# CircuitClockSchematic.net
KiCad netlist of a schematic drawn in EAGLE
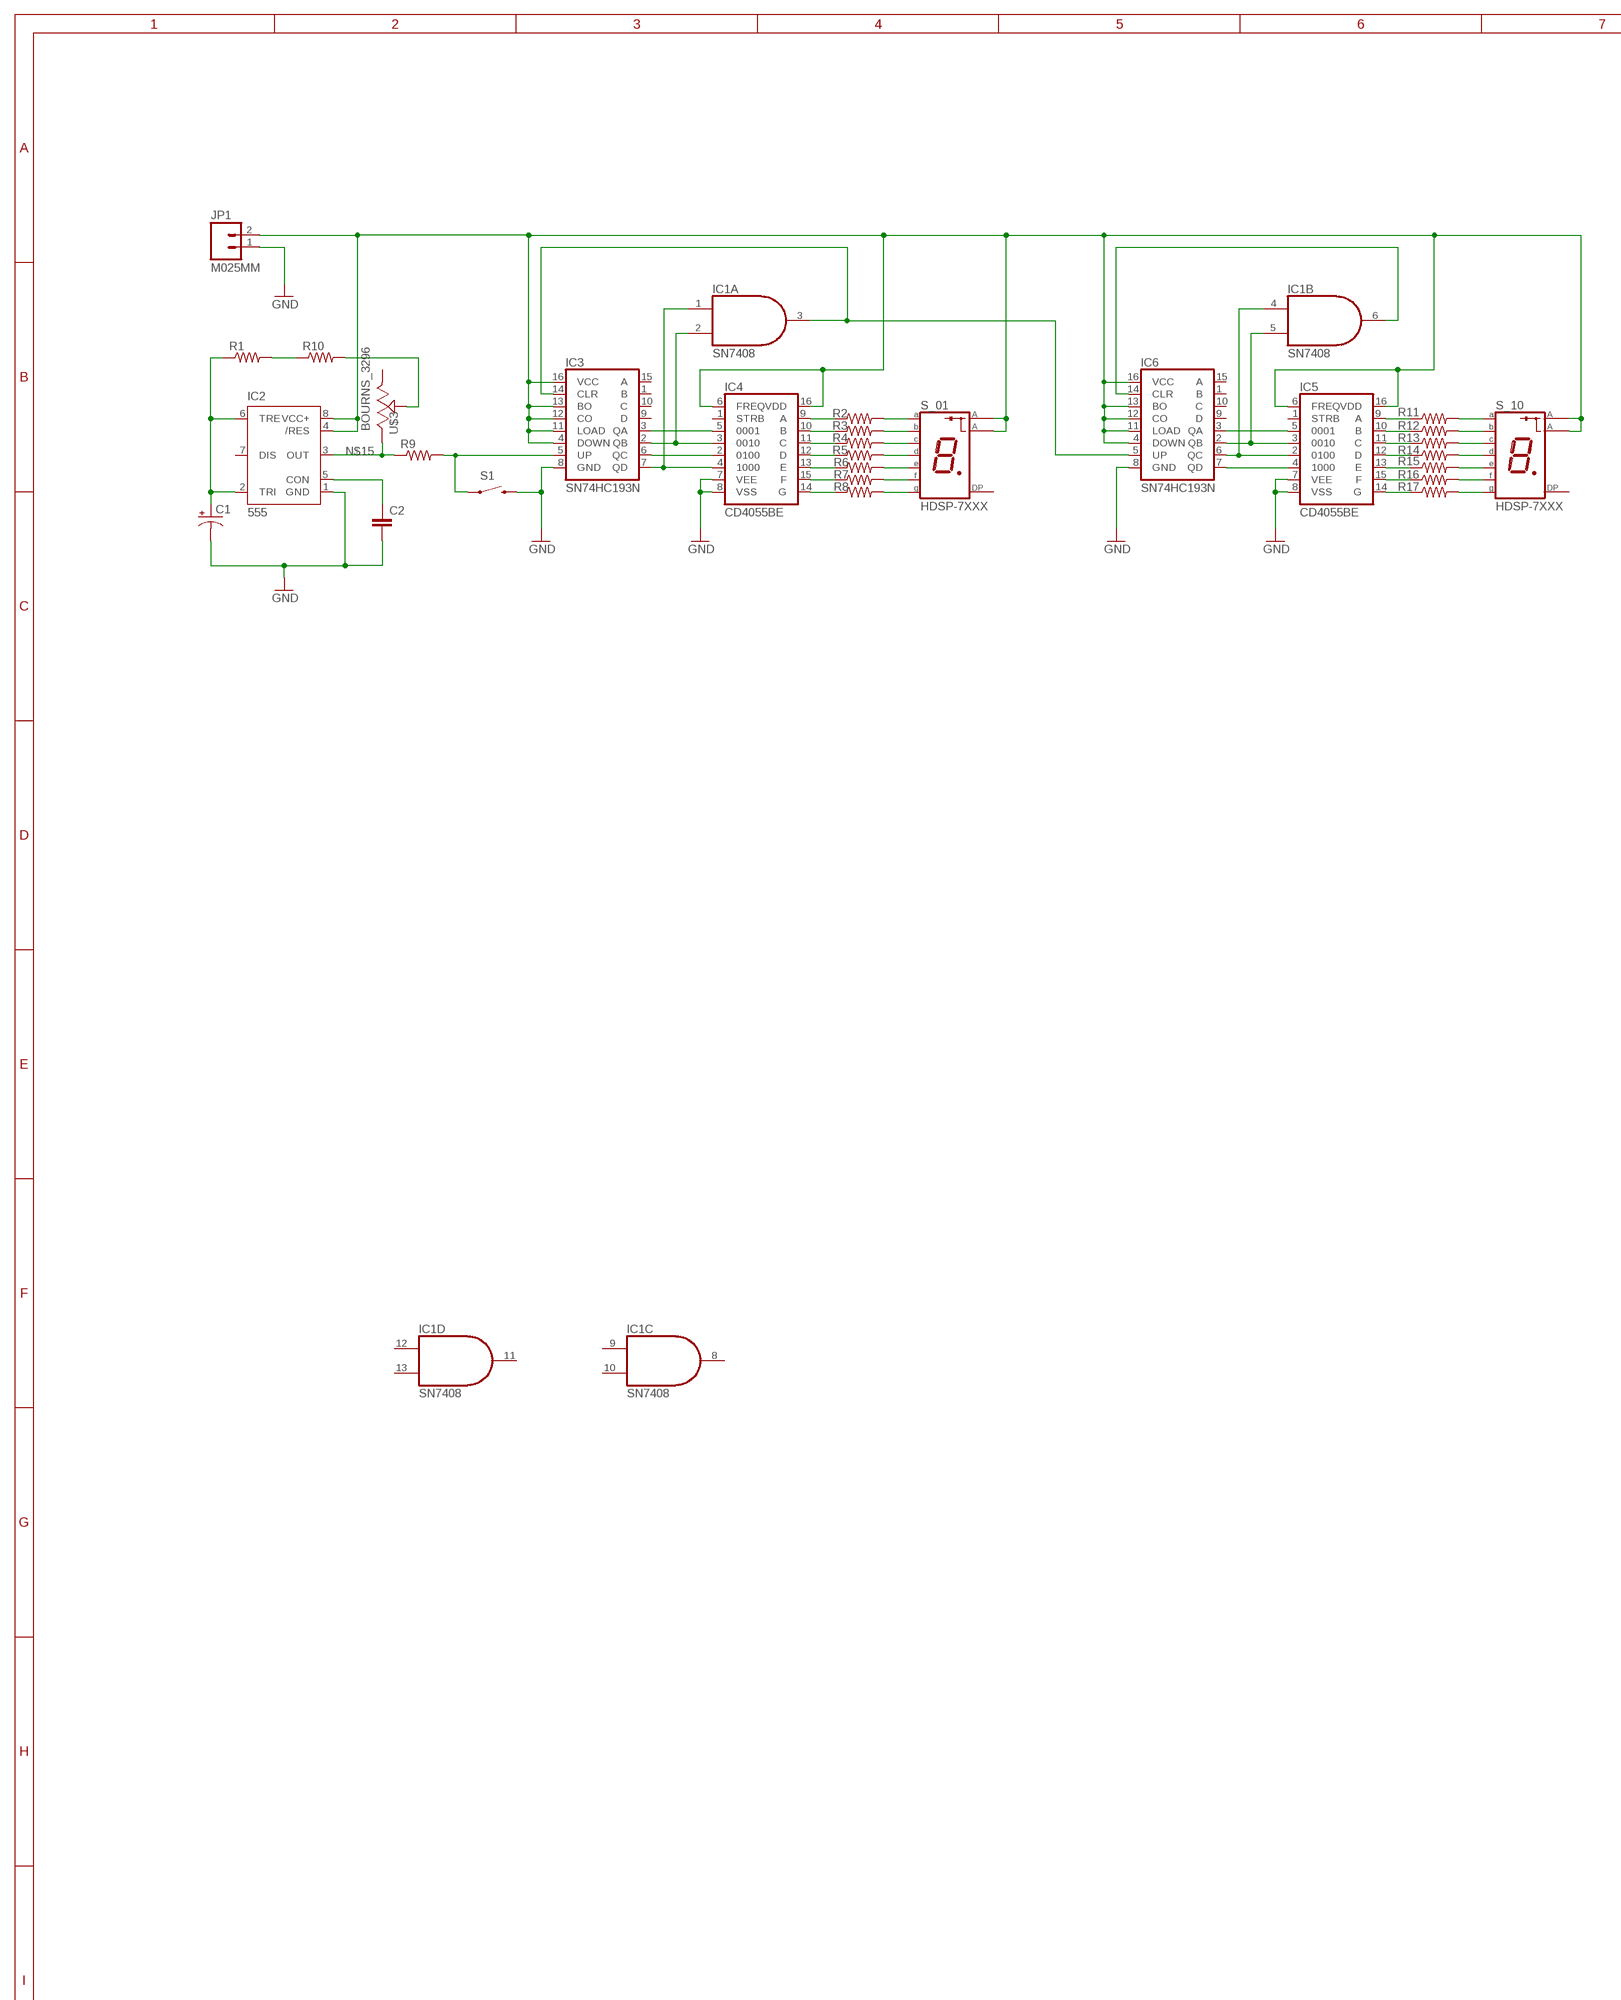
[diagram p0: schematic, sheet 1, part 1 of 2]
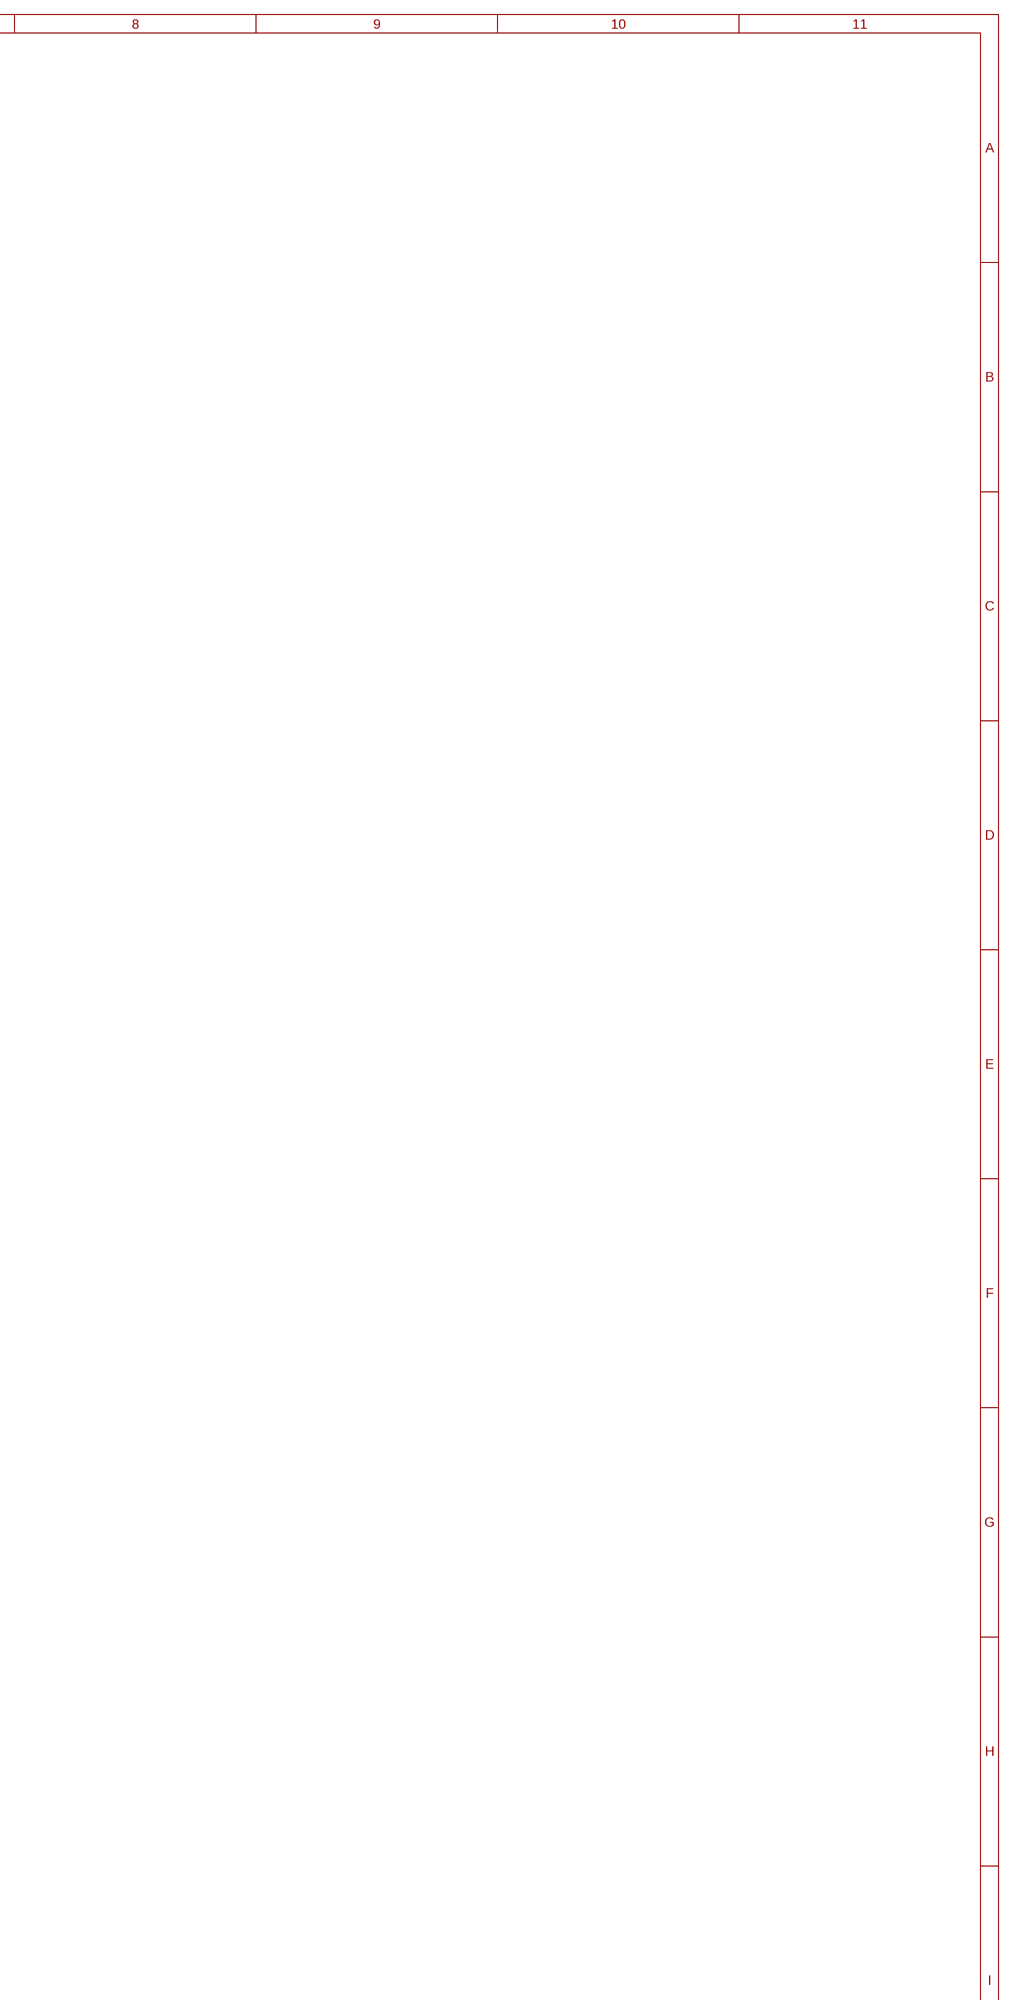
[diagram p1: schematic, sheet 1, part 2 of 2]

(export (version "E")
  (design (tool "Eeschema 10.0.6"))
  (components
    (comp (ref "C1")
      (value "RADIAL_POL2.54MM_LEAD-6.3MM_DIA")
      (footprint "eagle-import:2.54MM_LEAD-6.3MM_DIA")
      (libsource (lib "eagle-import") (part "RADIAL_POL2.54MM_LEAD-6.3MM_DIA"))
    )
    (comp (ref "C2")
      (value "CAPPTH")
      (footprint "eagle-import:CAP-PTH-SMALL")
      (libsource (lib "eagle-import") (part "CAPPTH"))
    )
    (comp (ref "IC1")
      (value "SN7408")
      (footprint "eagle-import:DIL14")
      (libsource (lib "eagle-import") (part "7408NS"))
    )
    (comp (ref "IC2")
      (value "555")
      (footprint "eagle-import:DIP08-KIT")
      (libsource (lib "eagle-import") (part "555KIT"))
    )
    (comp (ref "IC3")
      (value "SN74HC193N")
      (footprint "eagle-import:DIL16")
      (libsource (lib "eagle-import") (part "SN74HC193N"))
    )
    (comp (ref "IC4")
      (value "CD4055BE")
      (footprint "eagle-import:DIL16")
      (libsource (lib "eagle-import") (part "CD4055BE"))
    )
    (comp (ref "IC5")
      (value "CD4055BE")
      (footprint "eagle-import:DIL16")
      (libsource (lib "eagle-import") (part "CD4055BE"))
    )
    (comp (ref "IC6")
      (value "SN74HC193N")
      (footprint "eagle-import:DIL16")
      (libsource (lib "eagle-import") (part "SN74HC193N"))
    )
    (comp (ref "JP1")
      (value "M025MM")
      (footprint "eagle-import:SCREWTERMINAL-5MM-2")
      (libsource (lib "eagle-import") (part "M025MM"))
    )
    (comp (ref "R1")
      (value "RESISTORAXIAL-0.3")
      (footprint "eagle-import:AXIAL-0.3")
      (libsource (lib "eagle-import") (part "RESISTORAXIAL-0.3"))
    )
    (comp (ref "R2")
      (value "RESISTORAXIAL-0.3")
      (footprint "eagle-import:AXIAL-0.3")
      (libsource (lib "eagle-import") (part "RESISTORAXIAL-0.3"))
    )
    (comp (ref "R3")
      (value "RESISTORAXIAL-0.3")
      (footprint "eagle-import:AXIAL-0.3")
      (libsource (lib "eagle-import") (part "RESISTORAXIAL-0.3"))
    )
    (comp (ref "R4")
      (value "RESISTORAXIAL-0.3")
      (footprint "eagle-import:AXIAL-0.3")
      (libsource (lib "eagle-import") (part "RESISTORAXIAL-0.3"))
    )
    (comp (ref "R5")
      (value "RESISTORAXIAL-0.3")
      (footprint "eagle-import:AXIAL-0.3")
      (libsource (lib "eagle-import") (part "RESISTORAXIAL-0.3"))
    )
    (comp (ref "R6")
      (value "RESISTORAXIAL-0.3")
      (footprint "eagle-import:AXIAL-0.3")
      (libsource (lib "eagle-import") (part "RESISTORAXIAL-0.3"))
    )
    (comp (ref "R7")
      (value "RESISTORAXIAL-0.3")
      (footprint "eagle-import:AXIAL-0.3")
      (libsource (lib "eagle-import") (part "RESISTORAXIAL-0.3"))
    )
    (comp (ref "R8")
      (value "RESISTORAXIAL-0.3")
      (footprint "eagle-import:AXIAL-0.3")
      (libsource (lib "eagle-import") (part "RESISTORAXIAL-0.3"))
    )
    (comp (ref "R9")
      (value "RESISTORAXIAL-0.3")
      (footprint "eagle-import:AXIAL-0.3")
      (libsource (lib "eagle-import") (part "RESISTORAXIAL-0.3"))
    )
    (comp (ref "R10")
      (value "RESISTORAXIAL-0.3")
      (footprint "eagle-import:AXIAL-0.3")
      (libsource (lib "eagle-import") (part "RESISTORAXIAL-0.3"))
    )
    (comp (ref "R11")
      (value "RESISTORAXIAL-0.3")
      (footprint "eagle-import:AXIAL-0.3")
      (libsource (lib "eagle-import") (part "RESISTORAXIAL-0.3"))
    )
    (comp (ref "R12")
      (value "RESISTORAXIAL-0.3")
      (footprint "eagle-import:AXIAL-0.3")
      (libsource (lib "eagle-import") (part "RESISTORAXIAL-0.3"))
    )
    (comp (ref "R13")
      (value "RESISTORAXIAL-0.3")
      (footprint "eagle-import:AXIAL-0.3")
      (libsource (lib "eagle-import") (part "RESISTORAXIAL-0.3"))
    )
    (comp (ref "R14")
      (value "RESISTORAXIAL-0.3")
      (footprint "eagle-import:AXIAL-0.3")
      (libsource (lib "eagle-import") (part "RESISTORAXIAL-0.3"))
    )
    (comp (ref "R15")
      (value "RESISTORAXIAL-0.3")
      (footprint "eagle-import:AXIAL-0.3")
      (libsource (lib "eagle-import") (part "RESISTORAXIAL-0.3"))
    )
    (comp (ref "R16")
      (value "RESISTORAXIAL-0.3")
      (footprint "eagle-import:AXIAL-0.3")
      (libsource (lib "eagle-import") (part "RESISTORAXIAL-0.3"))
    )
    (comp (ref "R17")
      (value "RESISTORAXIAL-0.3")
      (footprint "eagle-import:AXIAL-0.3")
      (libsource (lib "eagle-import") (part "RESISTORAXIAL-0.3"))
    )
    (comp (ref "S1")
      (value "SWITCH-MOMENTARY-2PTH")
      (footprint "eagle-import:TACTILE-PTH")
      (libsource (lib "eagle-import") (part "SWITCH-MOMENTARY-2PTH"))
    )
    (comp (ref "S_01")
      (value "HDSP-7XXX")
      (footprint "eagle-import:HDSP-7XXX")
      (libsource (lib "eagle-import") (part "HDSP-7XXX"))
    )
    (comp (ref "S_10")
      (value "HDSP-7XXX")
      (footprint "eagle-import:HDSP-7XXX")
      (libsource (lib "eagle-import") (part "HDSP-7XXX"))
    )
    (comp (ref "U$3")
      (value "BOURNS_3296")
      (footprint "eagle-import:3296")
      (libsource (lib "eagle-import") (part "BOURNS_3296"))
    )
  )
  (nets
    (net (code "1") (name "/N$15") (class "Default")
      (node (ref "IC2") (pin "3") (pinfunction "OUT_3") (pintype "output"))
      (node (ref "R9") (pin "P$1") (pinfunction "1_P$1") (pintype "passive"))
      (node (ref "U$3") (pin "1") (pinfunction "A_1") (pintype "passive"))
    )
    (net (code "2") (name "GND") (class "Default")
      (node (ref "C1") (pin "-") (pinfunction "-_-") (pintype "passive"))
      (node (ref "C2") (pin "2") (pinfunction "2_2") (pintype "passive"))
      (node (ref "IC2") (pin "1") (pinfunction "GND_1") (pintype "power_in"))
      (node (ref "IC3") (pin "8") (pinfunction "GND_8") (pintype "power_in"))
      (node (ref "IC4") (pin "7") (pinfunction "VEE_7") (pintype "bidirectional"))
      (node (ref "IC4") (pin "8") (pinfunction "VSS_8") (pintype "power_in"))
      (node (ref "IC5") (pin "7") (pinfunction "VEE_7") (pintype "bidirectional"))
      (node (ref "IC5") (pin "8") (pinfunction "VSS_8") (pintype "power_in"))
      (node (ref "IC6") (pin "8") (pinfunction "GND_8") (pintype "power_in"))
      (node (ref "JP1") (pin "1") (pinfunction "1_1") (pintype "passive"))
      (node (ref "S1") (pin "3") (pinfunction "2_3") (pintype "passive"))
    )
    (net (code "3") (name "Net-(IC1A-I0)") (class "Default")
      (node (ref "IC1") (pin "1") (pinfunction "I0_1") (pintype "input"))
      (node (ref "IC3") (pin "7") (pinfunction "QD_7") (pintype "bidirectional"))
      (node (ref "IC4") (pin "4") (pinfunction "1000_4") (pintype "bidirectional"))
    )
    (net (code "4") (name "Net-(IC1A-I1)") (class "Default")
      (node (ref "IC1") (pin "2") (pinfunction "I1_2") (pintype "input"))
      (node (ref "IC3") (pin "2") (pinfunction "QB_2") (pintype "bidirectional"))
      (node (ref "IC4") (pin "3") (pinfunction "0010_3") (pintype "input"))
    )
    (net (code "5") (name "Net-(IC1A-O)") (class "Default")
      (node (ref "IC1") (pin "3") (pinfunction "O_3") (pintype "output"))
      (node (ref "IC3") (pin "14") (pinfunction "CLR_14") (pintype "bidirectional"))
      (node (ref "IC6") (pin "5") (pinfunction "UP_5") (pintype "bidirectional"))
    )
    (net (code "6") (name "Net-(IC1B-I0)") (class "Default")
      (node (ref "IC1") (pin "4") (pinfunction "I0_4") (pintype "input"))
      (node (ref "IC5") (pin "2") (pinfunction "0100_2") (pintype "input"))
      (node (ref "IC6") (pin "6") (pinfunction "QC_6") (pintype "bidirectional"))
    )
    (net (code "7") (name "Net-(IC1B-I1)") (class "Default")
      (node (ref "IC1") (pin "5") (pinfunction "I1_5") (pintype "input"))
      (node (ref "IC5") (pin "3") (pinfunction "0010_3") (pintype "input"))
      (node (ref "IC6") (pin "2") (pinfunction "QB_2") (pintype "bidirectional"))
    )
    (net (code "8") (name "Net-(IC1B-O)") (class "Default")
      (node (ref "IC1") (pin "6") (pinfunction "O_6") (pintype "output"))
      (node (ref "IC6") (pin "14") (pinfunction "CLR_14") (pintype "bidirectional"))
    )
    (net (code "9") (name "Net-(IC2-CON)") (class "Default")
      (node (ref "C2") (pin "1") (pinfunction "1_1") (pintype "passive"))
      (node (ref "IC2") (pin "5") (pinfunction "CON_5") (pintype "input"))
    )
    (net (code "10") (name "Net-(IC2-TRE)") (class "Default")
      (node (ref "C1") (pin "+") (pinfunction "+_+") (pintype "passive"))
      (node (ref "IC2") (pin "2") (pinfunction "TRI_2") (pintype "input"))
      (node (ref "IC2") (pin "6") (pinfunction "TRE_6") (pintype "input"))
      (node (ref "R1") (pin "P$1") (pinfunction "1_P$1") (pintype "passive"))
    )
    (net (code "11") (name "Net-(IC2-VCC+)") (class "Default")
      (node (ref "IC2") (pin "4") (pinfunction "/RES_4") (pintype "input"))
      (node (ref "IC2") (pin "8") (pinfunction "VCC+_8") (pintype "power_in"))
      (node (ref "IC3") (pin "11") (pinfunction "LOAD_11") (pintype "input"))
      (node (ref "IC3") (pin "12") (pinfunction "CO_12") (pintype "input"))
      (node (ref "IC3") (pin "13") (pinfunction "BO_13") (pintype "bidirectional"))
      (node (ref "IC3") (pin "16") (pinfunction "VCC_16") (pintype "power_in"))
      (node (ref "IC3") (pin "4") (pinfunction "DOWN_4") (pintype "input"))
      (node (ref "IC4") (pin "16") (pinfunction "VDD_16") (pintype "power_in"))
      (node (ref "IC4") (pin "6") (pinfunction "FREQ_6") (pintype "bidirectional"))
      (node (ref "IC5") (pin "16") (pinfunction "VDD_16") (pintype "power_in"))
      (node (ref "IC5") (pin "6") (pinfunction "FREQ_6") (pintype "bidirectional"))
      (node (ref "IC6") (pin "11") (pinfunction "LOAD_11") (pintype "input"))
      (node (ref "IC6") (pin "12") (pinfunction "CO_12") (pintype "input"))
      (node (ref "IC6") (pin "13") (pinfunction "BO_13") (pintype "bidirectional"))
      (node (ref "IC6") (pin "16") (pinfunction "VCC_16") (pintype "power_in"))
      (node (ref "IC6") (pin "4") (pinfunction "DOWN_4") (pintype "input"))
      (node (ref "JP1") (pin "2") (pinfunction "2_2") (pintype "passive"))
      (node (ref "S_01") (pin "P$1") (pinfunction "A_P$1") (pintype "passive"))
      (node (ref "S_01") (pin "P$6") (pinfunction "A_P$6") (pintype "passive"))
      (node (ref "S_10") (pin "P$1") (pinfunction "A_P$1") (pintype "passive"))
      (node (ref "S_10") (pin "P$6") (pinfunction "A_P$6") (pintype "passive"))
    )
    (net (code "12") (name "Net-(IC3-QA)") (class "Default")
      (node (ref "IC3") (pin "3") (pinfunction "QA_3") (pintype "bidirectional"))
      (node (ref "IC4") (pin "5") (pinfunction "0001_5") (pintype "input"))
    )
    (net (code "13") (name "Net-(IC3-QC)") (class "Default")
      (node (ref "IC3") (pin "6") (pinfunction "QC_6") (pintype "bidirectional"))
      (node (ref "IC4") (pin "2") (pinfunction "0100_2") (pintype "input"))
    )
    (net (code "14") (name "Net-(IC3-UP)") (class "Default")
      (node (ref "IC3") (pin "5") (pinfunction "UP_5") (pintype "bidirectional"))
      (node (ref "R9") (pin "P$2") (pinfunction "2_P$2") (pintype "passive"))
      (node (ref "S1") (pin "1") (pinfunction "1_1") (pintype "passive"))
    )
    (net (code "15") (name "Net-(IC4-A)") (class "Default")
      (node (ref "IC4") (pin "9") (pinfunction "A_9") (pintype "bidirectional"))
      (node (ref "R2") (pin "P$1") (pinfunction "1_P$1") (pintype "passive"))
    )
    (net (code "16") (name "Net-(IC4-B)") (class "Default")
      (node (ref "IC4") (pin "10") (pinfunction "B_10") (pintype "bidirectional"))
      (node (ref "R3") (pin "P$1") (pinfunction "1_P$1") (pintype "passive"))
    )
    (net (code "17") (name "Net-(IC4-C)") (class "Default")
      (node (ref "IC4") (pin "11") (pinfunction "C_11") (pintype "bidirectional"))
      (node (ref "R4") (pin "P$1") (pinfunction "1_P$1") (pintype "passive"))
    )
    (net (code "18") (name "Net-(IC4-D)") (class "Default")
      (node (ref "IC4") (pin "12") (pinfunction "D_12") (pintype "bidirectional"))
      (node (ref "R5") (pin "P$1") (pinfunction "1_P$1") (pintype "passive"))
    )
    (net (code "19") (name "Net-(IC4-E)") (class "Default")
      (node (ref "IC4") (pin "13") (pinfunction "E_13") (pintype "bidirectional"))
      (node (ref "R6") (pin "P$1") (pinfunction "1_P$1") (pintype "passive"))
    )
    (net (code "20") (name "Net-(IC4-F)") (class "Default")
      (node (ref "IC4") (pin "15") (pinfunction "F_15") (pintype "bidirectional"))
      (node (ref "R7") (pin "P$1") (pinfunction "1_P$1") (pintype "passive"))
    )
    (net (code "21") (name "Net-(IC4-G)") (class "Default")
      (node (ref "IC4") (pin "14") (pinfunction "G_14") (pintype "bidirectional"))
      (node (ref "R8") (pin "P$1") (pinfunction "1_P$1") (pintype "passive"))
    )
    (net (code "22") (name "Net-(IC5-0001)") (class "Default")
      (node (ref "IC5") (pin "5") (pinfunction "0001_5") (pintype "input"))
      (node (ref "IC6") (pin "3") (pinfunction "QA_3") (pintype "bidirectional"))
    )
    (net (code "23") (name "Net-(IC5-1000)") (class "Default")
      (node (ref "IC5") (pin "4") (pinfunction "1000_4") (pintype "bidirectional"))
      (node (ref "IC6") (pin "7") (pinfunction "QD_7") (pintype "bidirectional"))
    )
    (net (code "24") (name "Net-(IC5-A)") (class "Default")
      (node (ref "IC5") (pin "9") (pinfunction "A_9") (pintype "bidirectional"))
      (node (ref "R11") (pin "P$1") (pinfunction "1_P$1") (pintype "passive"))
    )
    (net (code "25") (name "Net-(IC5-B)") (class "Default")
      (node (ref "IC5") (pin "10") (pinfunction "B_10") (pintype "bidirectional"))
      (node (ref "R12") (pin "P$1") (pinfunction "1_P$1") (pintype "passive"))
    )
    (net (code "26") (name "Net-(IC5-C)") (class "Default")
      (node (ref "IC5") (pin "11") (pinfunction "C_11") (pintype "bidirectional"))
      (node (ref "R13") (pin "P$1") (pinfunction "1_P$1") (pintype "passive"))
    )
    (net (code "27") (name "Net-(IC5-D)") (class "Default")
      (node (ref "IC5") (pin "12") (pinfunction "D_12") (pintype "bidirectional"))
      (node (ref "R14") (pin "P$1") (pinfunction "1_P$1") (pintype "passive"))
    )
    (net (code "28") (name "Net-(IC5-E)") (class "Default")
      (node (ref "IC5") (pin "13") (pinfunction "E_13") (pintype "bidirectional"))
      (node (ref "R15") (pin "P$1") (pinfunction "1_P$1") (pintype "passive"))
    )
    (net (code "29") (name "Net-(IC5-F)") (class "Default")
      (node (ref "IC5") (pin "15") (pinfunction "F_15") (pintype "bidirectional"))
      (node (ref "R16") (pin "P$1") (pinfunction "1_P$1") (pintype "passive"))
    )
    (net (code "30") (name "Net-(IC5-G)") (class "Default")
      (node (ref "IC5") (pin "14") (pinfunction "G_14") (pintype "bidirectional"))
      (node (ref "R17") (pin "P$1") (pinfunction "1_P$1") (pintype "passive"))
    )
    (net (code "31") (name "Net-(R1-2)") (class "Default")
      (node (ref "R1") (pin "P$2") (pinfunction "2_P$2") (pintype "passive"))
      (node (ref "R10") (pin "P$1") (pinfunction "1_P$1") (pintype "passive"))
    )
    (net (code "32") (name "Net-(R2-2)") (class "Default")
      (node (ref "R2") (pin "P$2") (pinfunction "2_P$2") (pintype "passive"))
      (node (ref "S_01") (pin "P$10") (pinfunction "A_P$10") (pintype "passive"))
    )
    (net (code "33") (name "Net-(R3-2)") (class "Default")
      (node (ref "R3") (pin "P$2") (pinfunction "2_P$2") (pintype "passive"))
      (node (ref "S_01") (pin "P$9") (pinfunction "B_P$9") (pintype "passive"))
    )
    (net (code "34") (name "Net-(R4-2)") (class "Default")
      (node (ref "R4") (pin "P$2") (pinfunction "2_P$2") (pintype "passive"))
      (node (ref "S_01") (pin "P$8") (pinfunction "C_P$8") (pintype "passive"))
    )
    (net (code "35") (name "Net-(R5-2)") (class "Default")
      (node (ref "R5") (pin "P$2") (pinfunction "2_P$2") (pintype "passive"))
      (node (ref "S_01") (pin "P$5") (pinfunction "D_P$5") (pintype "passive"))
    )
    (net (code "36") (name "Net-(R6-2)") (class "Default")
      (node (ref "R6") (pin "P$2") (pinfunction "2_P$2") (pintype "passive"))
      (node (ref "S_01") (pin "P$4") (pinfunction "E_P$4") (pintype "passive"))
    )
    (net (code "37") (name "Net-(R7-2)") (class "Default")
      (node (ref "R7") (pin "P$2") (pinfunction "2_P$2") (pintype "passive"))
      (node (ref "S_01") (pin "P$2") (pinfunction "F_P$2") (pintype "passive"))
    )
    (net (code "38") (name "Net-(R8-2)") (class "Default")
      (node (ref "R8") (pin "P$2") (pinfunction "2_P$2") (pintype "passive"))
      (node (ref "S_01") (pin "P$3") (pinfunction "G_P$3") (pintype "passive"))
    )
    (net (code "39") (name "Net-(R10-2)") (class "Default")
      (node (ref "R10") (pin "P$2") (pinfunction "2_P$2") (pintype "passive"))
      (node (ref "U$3") (pin "2") (pinfunction "S_2") (pintype "passive"))
    )
    (net (code "40") (name "Net-(R11-2)") (class "Default")
      (node (ref "R11") (pin "P$2") (pinfunction "2_P$2") (pintype "passive"))
      (node (ref "S_10") (pin "P$10") (pinfunction "A_P$10") (pintype "passive"))
    )
    (net (code "41") (name "Net-(R12-2)") (class "Default")
      (node (ref "R12") (pin "P$2") (pinfunction "2_P$2") (pintype "passive"))
      (node (ref "S_10") (pin "P$9") (pinfunction "B_P$9") (pintype "passive"))
    )
    (net (code "42") (name "Net-(R13-2)") (class "Default")
      (node (ref "R13") (pin "P$2") (pinfunction "2_P$2") (pintype "passive"))
      (node (ref "S_10") (pin "P$8") (pinfunction "C_P$8") (pintype "passive"))
    )
    (net (code "43") (name "Net-(R14-2)") (class "Default")
      (node (ref "R14") (pin "P$2") (pinfunction "2_P$2") (pintype "passive"))
      (node (ref "S_10") (pin "P$5") (pinfunction "D_P$5") (pintype "passive"))
    )
    (net (code "44") (name "Net-(R15-2)") (class "Default")
      (node (ref "R15") (pin "P$2") (pinfunction "2_P$2") (pintype "passive"))
      (node (ref "S_10") (pin "P$4") (pinfunction "E_P$4") (pintype "passive"))
    )
    (net (code "45") (name "Net-(R16-2)") (class "Default")
      (node (ref "R16") (pin "P$2") (pinfunction "2_P$2") (pintype "passive"))
      (node (ref "S_10") (pin "P$2") (pinfunction "F_P$2") (pintype "passive"))
    )
    (net (code "46") (name "Net-(R17-2)") (class "Default")
      (node (ref "R17") (pin "P$2") (pinfunction "2_P$2") (pintype "passive"))
      (node (ref "S_10") (pin "P$3") (pinfunction "G_P$3") (pintype "passive"))
    )
    (net (code "47") (name "unconnected-(IC1C-I0-Pad9)") (class "Default")
      (node (ref "IC1") (pin "9") (pinfunction "I0_9") (pintype "input"))
    )
    (net (code "48") (name "unconnected-(IC1C-I1-Pad10)") (class "Default")
      (node (ref "IC1") (pin "10") (pinfunction "I1_10") (pintype "input"))
    )
    (net (code "49") (name "unconnected-(IC1C-O-Pad8)") (class "Default")
      (node (ref "IC1") (pin "8") (pinfunction "O_8") (pintype "output"))
    )
    (net (code "50") (name "unconnected-(IC1D-I0-Pad12)") (class "Default")
      (node (ref "IC1") (pin "12") (pinfunction "I0_12") (pintype "input"))
    )
    (net (code "51") (name "unconnected-(IC1D-I1-Pad13)") (class "Default")
      (node (ref "IC1") (pin "13") (pinfunction "I1_13") (pintype "input"))
    )
    (net (code "52") (name "unconnected-(IC1D-O-Pad11)") (class "Default")
      (node (ref "IC1") (pin "11") (pinfunction "O_11") (pintype "output"))
    )
    (net (code "53") (name "unconnected-(IC2-DIS-Pad7)") (class "Default")
      (node (ref "IC2") (pin "7") (pinfunction "DIS_7") (pintype "input"))
    )
    (net (code "54") (name "unconnected-(IC3-A-Pad15)") (class "Default")
      (node (ref "IC3") (pin "15") (pinfunction "A_15") (pintype "bidirectional"))
    )
    (net (code "55") (name "unconnected-(IC3-B-Pad1)") (class "Default")
      (node (ref "IC3") (pin "1") (pinfunction "B_1") (pintype "bidirectional"))
    )
    (net (code "56") (name "unconnected-(IC3-C-Pad10)") (class "Default")
      (node (ref "IC3") (pin "10") (pinfunction "C_10") (pintype "bidirectional"))
    )
    (net (code "57") (name "unconnected-(IC3-D-Pad9)") (class "Default")
      (node (ref "IC3") (pin "9") (pinfunction "D_9") (pintype "bidirectional"))
    )
    (net (code "58") (name "unconnected-(IC4-STRB-Pad1)") (class "Default")
      (node (ref "IC4") (pin "1") (pinfunction "STRB_1") (pintype "bidirectional"))
    )
    (net (code "59") (name "unconnected-(IC5-STRB-Pad1)") (class "Default")
      (node (ref "IC5") (pin "1") (pinfunction "STRB_1") (pintype "bidirectional"))
    )
    (net (code "60") (name "unconnected-(IC6-A-Pad15)") (class "Default")
      (node (ref "IC6") (pin "15") (pinfunction "A_15") (pintype "bidirectional"))
    )
    (net (code "61") (name "unconnected-(IC6-B-Pad1)") (class "Default")
      (node (ref "IC6") (pin "1") (pinfunction "B_1") (pintype "bidirectional"))
    )
    (net (code "62") (name "unconnected-(IC6-C-Pad10)") (class "Default")
      (node (ref "IC6") (pin "10") (pinfunction "C_10") (pintype "bidirectional"))
    )
    (net (code "63") (name "unconnected-(IC6-D-Pad9)") (class "Default")
      (node (ref "IC6") (pin "9") (pinfunction "D_9") (pintype "bidirectional"))
    )
    (net (code "64") (name "unconnected-(S_01-DP-PadP$7)") (class "Default")
      (node (ref "S_01") (pin "P$7") (pinfunction "DP_P$7") (pintype "passive"))
    )
    (net (code "65") (name "unconnected-(S_10-DP-PadP$7)") (class "Default")
      (node (ref "S_10") (pin "P$7") (pinfunction "DP_P$7") (pintype "passive"))
    )
    (net (code "66") (name "unconnected-(U$3-E-Pad3)") (class "Default")
      (node (ref "U$3") (pin "3") (pinfunction "E_3") (pintype "passive"))
    )
  )
)
